# Pompe_de_charge.net
KiCad netlist of a schematic drawn in Altium Designer
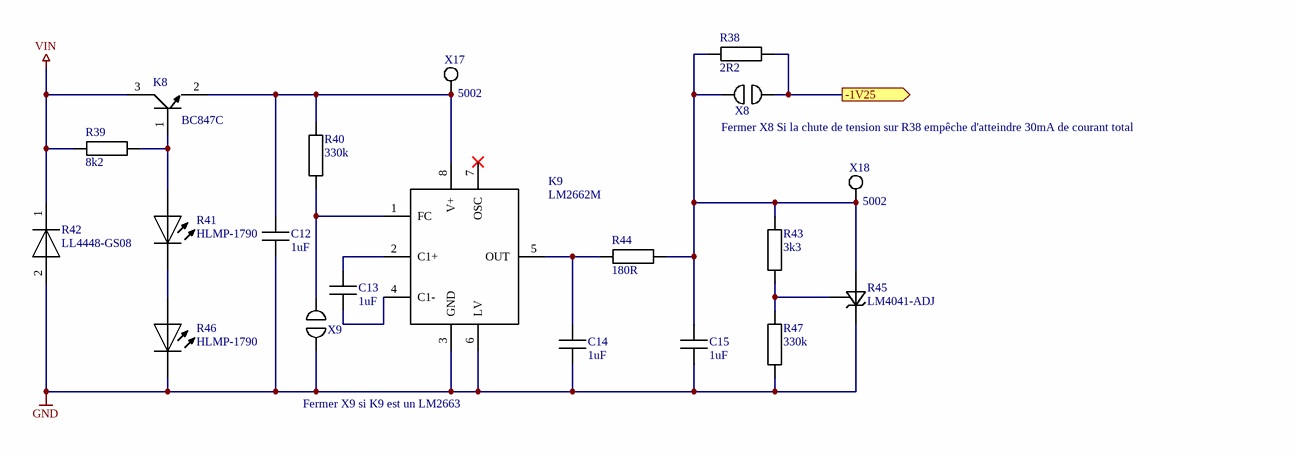
[diagram p0: Pompe de charge.SchDoc]

(export (version "E")
  (design (tool "Eeschema 10.0.6"))
  (components
    (comp (ref "C12")
      (value "1uF")
      (footprint "CAPC2012X08M")
      (description "CAPC 1uF X5R 25V 10% 2012 (0805 INCH)")
      (fields (field (name "MANUFACTURER") "TDK") (field (name "TOLERANCE") "±10%"))
      (libsource (lib "ETML-ES") (part "CAP"))
    )
    (comp (ref "C13")
      (value "1uF")
      (footprint "CAPC2012X08M")
      (description "CAPC 1uF X5R 25V 10% 2012 (0805 INCH)")
      (fields (field (name "MANUFACTURER") "TDK") (field (name "TOLERANCE") "±10%"))
      (libsource (lib "ETML-ES") (part "CAP"))
    )
    (comp (ref "C14")
      (value "1uF")
      (footprint "CAPC2012X08M")
      (description "CAPC 1uF X5R 25V 10% 2012 (0805 INCH)")
      (fields (field (name "MANUFACTURER") "TDK") (field (name "TOLERANCE") "±10%"))
      (libsource (lib "ETML-ES") (part "CAP"))
    )
    (comp (ref "C15")
      (value "1uF")
      (footprint "CAPC2012X08M")
      (description "CAPC 1uF X5R 25V 10% 2012 (0805 INCH)")
      (fields (field (name "MANUFACTURER") "TDK") (field (name "TOLERANCE") "±10%"))
      (libsource (lib "ETML-ES") (part "CAP"))
    )
    (comp (ref "K8")
      (value "BC847C")
      (footprint "SOT90P240X110-3M")
      (description "NPN general purpose transistor")
      (libsource (lib "Custom components") (part "BC847C"))
    )
    (comp (ref "K9")
      (value "LM2662M")
      (footprint "D0008A_M")
      (description "Switched Capacitor Voltage Converter, 8-pin Narrow SOIC")
      (fields (field (name "MANUFACTURER") "Texas Instruments"))
      (libsource (lib "Custom components") (part "LM2662M"))
    )
    (comp (ref "R38")
      (value "2R2")
      (footprint "RESC2012X06M")
      (description "RES 2.2ohm  ±1% 0.125W 2012 (0805 INCH)")
      (fields (field (name "VOLTAGE") "150V") (field (name "POWER") "0.125W"))
      (libsource (lib "ETML-ES") (part "RES"))
    )
    (comp (ref "R39")
      (value "8k2")
      (footprint "RESC2012X06M")
      (description "RES 8.2kohm  ±1% 0.125W 2012 (0805 INCH)")
      (fields (field (name "TOLERANCE") "±1%") (field (name "MANUFACTURER") "Yageo"))
      (libsource (lib "ETML-ES") (part "RES"))
    )
    (comp (ref "R40")
      (value "330k")
      (footprint "RESC2012X06M")
      (description "RES 330kohm  ±1% 0.125W 2012 (0805 INCH)")
      (fields (field (name "TOLERANCE") "±1%") (field (name "MANUFACTURER") "Yageo"))
      (libsource (lib "ETML-ES") (part "RES"))
    )
    (comp (ref "R41")
      (value "HLMP-1790")
      (footprint "FP-6_544-5255_01-4-MFG")
      (description "HLMP-1790 2V 2mA")
      (libsource (lib "Custom components") (part "HLMP-1790"))
    )
    (comp (ref "R42")
      (value "LL4448-GS08")
      (footprint "FP-6_560-5005_01-4-MFG")
      (description "DIODE GEN PURP 75V 150MA SOD80")
      (fields
        (field (name "MANUFACTURER") "Vishay Small Signal")
        (field (name "OCTOPART") "https://octopart.com/ll4448-gs08-vishay+small+signal-40886")
      )
      (libsource (lib "Custom components") (part "LL4448-GS08"))
    )
    (comp (ref "R43")
      (value "3k3")
      (footprint "RESC2012X06M")
      (description "RES 3.3kohm  ±1% 0.125W 2012 (0805 INCH)")
      (fields (field (name "VOLTAGE") "150V") (field (name "POWER") "0.125W"))
      (libsource (lib "ETML-ES") (part "RES"))
    )
    (comp (ref "R44")
      (value "180R")
      (footprint "RESC2012X06M")
      (description "RES 180ohm  ±1% 0.125W 2012 (0805 INCH)")
      (fields (field (name "POWER") "0.125W") (field (name "TOLERANCE") "±1%"))
      (libsource (lib "ETML-ES") (part "RES"))
    )
    (comp (ref "R45")
      (value "LM4041-ADJ")
      (footprint "SOT90P240X110-3M")
      (description "Precision Micropower Shunt Voltage Reference, 3-pin SOT-23")
      (fields (field (name "MANUFACTURER") "Texas Instruments"))
      (libsource (lib "Custom components") (part "LM4041"))
    )
    (comp (ref "R46")
      (value "HLMP-1790")
      (footprint "FP-6_544-5255_01-4-MFG")
      (description "HLMP-1790 2V 2mA")
      (libsource (lib "Custom components") (part "HLMP-1790"))
    )
    (comp (ref "R47")
      (value "330k")
      (footprint "RESC2012X06M")
      (description "RES 330kohm  ±1% 0.125W 2012 (0805 INCH)")
      (fields (field (name "TOLERANCE") "±1%") (field (name "MANUFACTURER") "Yageo"))
      (libsource (lib "ETML-ES") (part "RES"))
    )
    (comp (ref "X8")
      (value "Solder bridge")
      (footprint "Solder brige")
      (libsource (lib "Custom components") (part "Solder bridge"))
    )
    (comp (ref "X9")
      (value "Solder bridge")
      (footprint "Solder brige")
      (libsource (lib "Custom components") (part "Solder bridge"))
    )
    (comp (ref "X17")
      (value "5002")
      (footprint "Keystone_5002")
      (description "TEST THT MINIATURE WT")
      (fields (field (name "MANUFACTURER") "Keystone"))
      (libsource (lib "Custom components") (part "TEST"))
    )
    (comp (ref "X18")
      (value "5002")
      (footprint "Keystone_5002")
      (description "TEST THT MINIATURE WT")
      (fields (field (name "MANUFACTURER") "Keystone"))
      (libsource (lib "Custom components") (part "TEST"))
    )
  )
  (nets
    (net (code "1") (name "/-1V25") (class "Default")
      (node (ref "R38") (pin "2") (pinfunction "2_2") (pintype "passive"))
      (node (ref "X8") (pin "1") (pinfunction "1_1") (pintype "passive"))
    )
    (net (code "2") (name "GND") (class "Default")
      (node (ref "C12") (pin "1") (pinfunction "1_1") (pintype "passive"))
      (node (ref "C14") (pin "1") (pinfunction "1_1") (pintype "passive"))
      (node (ref "C15") (pin "1") (pinfunction "1_1") (pintype "passive"))
      (node (ref "K9") (pin "3") (pinfunction "GND_3") (pintype "power_in"))
      (node (ref "K9") (pin "6") (pinfunction "LV_6") (pintype "power_in"))
      (node (ref "R42") (pin "2") (pinfunction "A_2") (pintype "passive"))
      (node (ref "R45") (pin "2") (pinfunction "+V_2") (pintype "passive"))
      (node (ref "R46") (pin "K") (pinfunction "K_K") (pintype "passive"))
      (node (ref "R47") (pin "1") (pinfunction "1_1") (pintype "passive"))
      (node (ref "X9") (pin "1") (pinfunction "1_1") (pintype "passive"))
    )
    (net (code "3") (name "Net-(K8-Base)") (class "Default")
      (node (ref "K8") (pin "1") (pinfunction "Base_1") (pintype "passive"))
      (node (ref "R39") (pin "2") (pinfunction "2_2") (pintype "passive"))
      (node (ref "R41") (pin "A") (pinfunction "A_A") (pintype "passive"))
    )
    (net (code "4") (name "Net-(K8-Collector)") (class "Default")
      (node (ref "C12") (pin "2") (pinfunction "2_2") (pintype "passive"))
      (node (ref "K8") (pin "2") (pinfunction "Collector_2") (pintype "passive"))
      (node (ref "K9") (pin "8") (pinfunction "V+_8") (pintype "power_in"))
      (node (ref "R40") (pin "2") (pinfunction "2_2") (pintype "passive"))
      (node (ref "X17") (pin "1") (pinfunction "TP_1") (pintype "passive"))
    )
    (net (code "5") (name "Net-(K9-C1+)") (class "Default")
      (node (ref "C13") (pin "2") (pinfunction "2_2") (pintype "passive"))
      (node (ref "K9") (pin "2") (pinfunction "C1+_2") (pintype "power_in"))
    )
    (net (code "6") (name "Net-(K9-C1-)") (class "Default")
      (node (ref "C13") (pin "1") (pinfunction "1_1") (pintype "passive"))
      (node (ref "K9") (pin "4") (pinfunction "C1-_4") (pintype "power_in"))
    )
    (net (code "7") (name "Net-(K9-FC)") (class "Default")
      (node (ref "K9") (pin "1") (pinfunction "FC_1") (pintype "power_in"))
      (node (ref "R40") (pin "1") (pinfunction "1_1") (pintype "passive"))
      (node (ref "X9") (pin "2") (pinfunction "2_2") (pintype "passive"))
    )
    (net (code "8") (name "Net-(K9-OUT)") (class "Default")
      (node (ref "C14") (pin "2") (pinfunction "2_2") (pintype "passive"))
      (node (ref "K9") (pin "5") (pinfunction "OUT_5") (pintype "power_in"))
      (node (ref "R44") (pin "1") (pinfunction "1_1") (pintype "passive"))
    )
    (net (code "9") (name "Net-(R41-PadK)") (class "Default")
      (node (ref "R41") (pin "K") (pinfunction "K_K") (pintype "passive"))
      (node (ref "R46") (pin "A") (pinfunction "A_A") (pintype "passive"))
    )
    (net (code "10") (name "Net-(R45--V)") (class "Default")
      (node (ref "C15") (pin "2") (pinfunction "2_2") (pintype "passive"))
      (node (ref "R38") (pin "1") (pinfunction "1_1") (pintype "passive"))
      (node (ref "R43") (pin "2") (pinfunction "2_2") (pintype "passive"))
      (node (ref "R44") (pin "2") (pinfunction "2_2") (pintype "passive"))
      (node (ref "R45") (pin "3") (pinfunction "-V_3") (pintype "passive"))
      (node (ref "X18") (pin "1") (pinfunction "TP_1") (pintype "passive"))
      (node (ref "X8") (pin "2") (pinfunction "2_2") (pintype "passive"))
    )
    (net (code "11") (name "Net-(R45-FB)") (class "Default")
      (node (ref "R43") (pin "1") (pinfunction "1_1") (pintype "passive"))
      (node (ref "R45") (pin "1") (pinfunction "FB_1") (pintype "power_in"))
      (node (ref "R47") (pin "2") (pinfunction "2_2") (pintype "passive"))
    )
    (net (code "12") (name "VIN") (class "Default")
      (node (ref "K8") (pin "3") (pinfunction "Emitter_3") (pintype "passive"))
      (node (ref "R39") (pin "1") (pinfunction "1_1") (pintype "passive"))
      (node (ref "R42") (pin "1") (pinfunction "C_1") (pintype "passive"))
    )
    (net (code "13") (name "unconnected-(K9-OSC-Pad7)") (class "Default")
      (node (ref "K9") (pin "7") (pinfunction "OSC_7") (pintype "power_in+no_connect"))
    )
  )
)
